# esp-sme.net
KiCad netlist of a schematic drawn in EAGLE
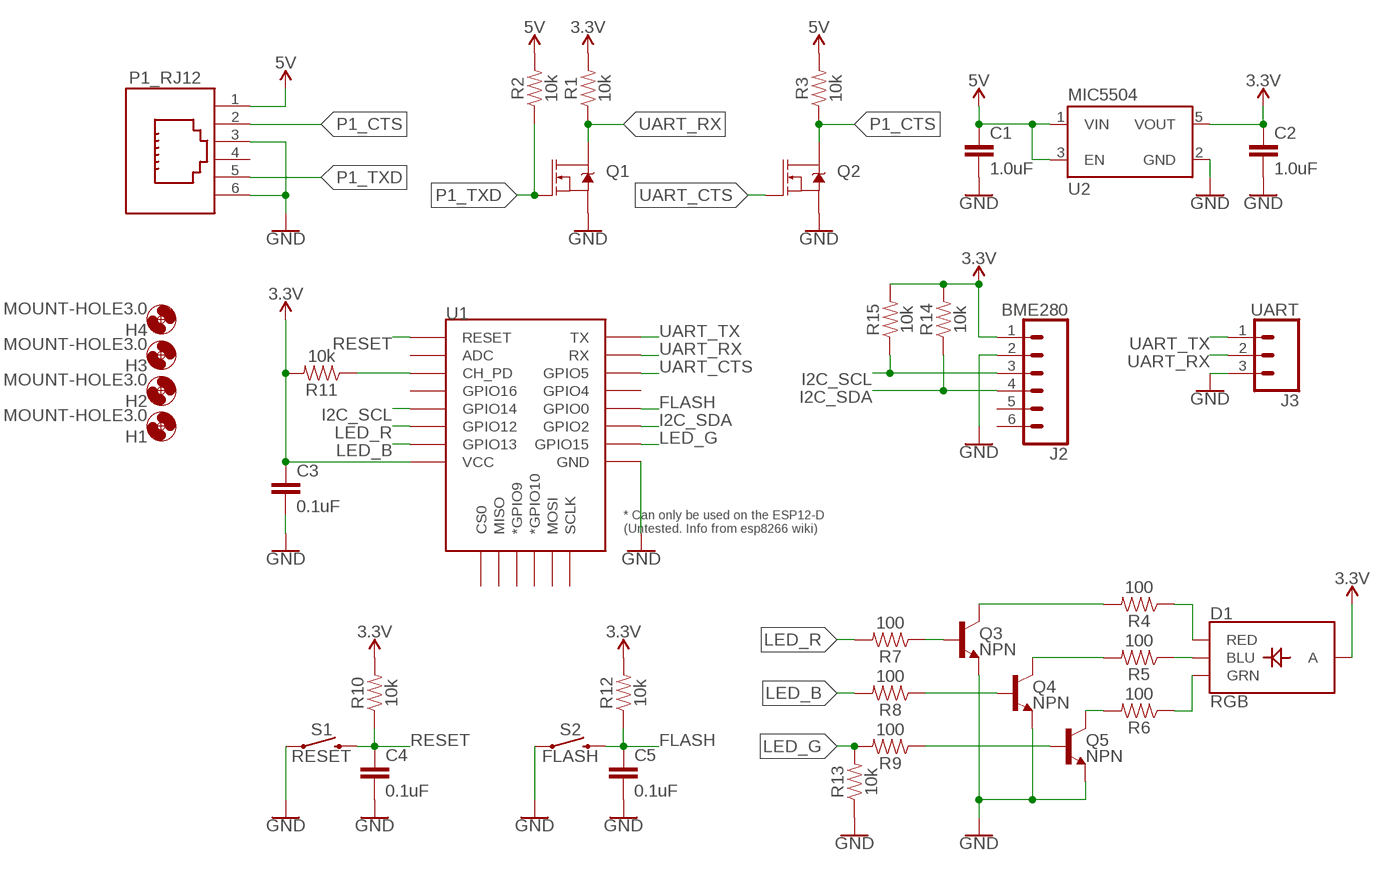
[diagram p0: schematic, sheet 1]

(export (version "E")
  (design (tool "Eeschema 10.0.6"))
  (components
    (comp (ref "C1")
      (value "1.0uF")
      (footprint "eagle-import:0603")
      (libsource (lib "eagle-import") (part "1.0UF-0603-16V-10%"))
    )
    (comp (ref "C2")
      (value "1.0uF")
      (footprint "eagle-import:0603")
      (libsource (lib "eagle-import") (part "1.0UF-0603-16V-10%"))
    )
    (comp (ref "C3")
      (value "0.1uF")
      (footprint "eagle-import:0603")
      (libsource (lib "eagle-import") (part "0.1UF-0603-25V-5%"))
    )
    (comp (ref "C4")
      (value "0.1uF")
      (footprint "eagle-import:0603")
      (libsource (lib "eagle-import") (part "0.1UF-0603-25V-5%"))
    )
    (comp (ref "C5")
      (value "0.1uF")
      (footprint "eagle-import:0603")
      (libsource (lib "eagle-import") (part "0.1UF-0603-25V-5%"))
    )
    (comp (ref "D1")
      (value "RGB")
      (footprint "eagle-import:P-LCC-4-3")
      (libsource (lib "eagle-import") (part "LED-RGB-CAPLCC"))
    )
    (comp (ref "H1")
      (value "MOUNT-HOLE3.0")
      (footprint "eagle-import:3,0")
      (libsource (lib "eagle-import") (part "MOUNT-HOLE3.0"))
    )
    (comp (ref "H2")
      (value "MOUNT-HOLE3.0")
      (footprint "eagle-import:3,0")
      (libsource (lib "eagle-import") (part "MOUNT-HOLE3.0"))
    )
    (comp (ref "H3")
      (value "MOUNT-HOLE3.0")
      (footprint "eagle-import:3,0")
      (libsource (lib "eagle-import") (part "MOUNT-HOLE3.0"))
    )
    (comp (ref "H4")
      (value "MOUNT-HOLE3.0")
      (footprint "eagle-import:3,0")
      (libsource (lib "eagle-import") (part "MOUNT-HOLE3.0"))
    )
    (comp (ref "J2")
      (value "BME280")
      (footprint "eagle-import:1X06")
      (libsource (lib "eagle-import") (part "CONN_06SILK_FEMALE_PTH"))
    )
    (comp (ref "J3")
      (value "UART")
      (footprint "eagle-import:1X03")
      (libsource (lib "eagle-import") (part "CONN_03"))
    )
    (comp (ref "P1_RJ12")
      (value "615006143621")
      (footprint "eagle-import:615006143621")
      (libsource (lib "eagle-import") (part "615006143621"))
    )
    (comp (ref "Q1")
      (value "MOSFET-NCH-AO3404A")
      (footprint "eagle-import:SOT23-3")
      (libsource (lib "eagle-import") (part "MOSFET-NCH-AO3404A"))
    )
    (comp (ref "Q2")
      (value "MOSFET-NCH-AO3404A")
      (footprint "eagle-import:SOT23-3")
      (libsource (lib "eagle-import") (part "MOSFET-NCH-AO3404A"))
    )
    (comp (ref "Q3")
      (value "NPN")
      (footprint "eagle-import:SOT23-3")
      (libsource (lib "eagle-import") (part "TRANS_NPN-MMBT2222AL"))
    )
    (comp (ref "Q4")
      (value "NPN")
      (footprint "eagle-import:SOT23-3")
      (libsource (lib "eagle-import") (part "TRANS_NPN-MMBT2222AL"))
    )
    (comp (ref "Q5")
      (value "NPN")
      (footprint "eagle-import:SOT23-3")
      (libsource (lib "eagle-import") (part "TRANS_NPN-MMBT2222AL"))
    )
    (comp (ref "R1")
      (value "10k")
      (footprint "eagle-import:0603")
      (libsource (lib "eagle-import") (part "10KOHM-0603-1/10W-1%"))
    )
    (comp (ref "R2")
      (value "10k")
      (footprint "eagle-import:0603")
      (libsource (lib "eagle-import") (part "10KOHM-0603-1/10W-1%"))
    )
    (comp (ref "R3")
      (value "10k")
      (footprint "eagle-import:0603")
      (libsource (lib "eagle-import") (part "10KOHM-0603-1/10W-1%"))
    )
    (comp (ref "R4")
      (value "100")
      (footprint "eagle-import:0603")
      (libsource (lib "eagle-import") (part "100OHM-0603-1/10W-1%"))
    )
    (comp (ref "R5")
      (value "100")
      (footprint "eagle-import:0603")
      (libsource (lib "eagle-import") (part "100OHM-0603-1/10W-1%"))
    )
    (comp (ref "R6")
      (value "100")
      (footprint "eagle-import:0603")
      (libsource (lib "eagle-import") (part "100OHM-0603-1/10W-1%"))
    )
    (comp (ref "R7")
      (value "100")
      (footprint "eagle-import:0603")
      (libsource (lib "eagle-import") (part "100OHM-0603-1/10W-1%"))
    )
    (comp (ref "R8")
      (value "100")
      (footprint "eagle-import:0603")
      (libsource (lib "eagle-import") (part "100OHM-0603-1/10W-1%"))
    )
    (comp (ref "R9")
      (value "100")
      (footprint "eagle-import:0603")
      (libsource (lib "eagle-import") (part "100OHM-0603-1/10W-1%"))
    )
    (comp (ref "R10")
      (value "10k")
      (footprint "eagle-import:0603")
      (libsource (lib "eagle-import") (part "10KOHM-0603-1/10W-1%"))
    )
    (comp (ref "R11")
      (value "10k")
      (footprint "eagle-import:0603")
      (libsource (lib "eagle-import") (part "10KOHM-0603-1/10W-1%"))
    )
    (comp (ref "R12")
      (value "10k")
      (footprint "eagle-import:0603")
      (libsource (lib "eagle-import") (part "10KOHM-0603-1/10W-1%"))
    )
    (comp (ref "R13")
      (value "10k")
      (footprint "eagle-import:0603")
      (libsource (lib "eagle-import") (part "10KOHM-0603-1/10W-1%"))
    )
    (comp (ref "R14")
      (value "10k")
      (footprint "eagle-import:0603")
      (libsource (lib "eagle-import") (part "10KOHM-0603-1/10W-1%"))
    )
    (comp (ref "R15")
      (value "10k")
      (footprint "eagle-import:0603")
      (libsource (lib "eagle-import") (part "10KOHM-0603-1/10W-1%"))
    )
    (comp (ref "S1")
      (value "RESET")
      (footprint "eagle-import:TACTILE_SWITCH_SMD_4.6X2.8MM")
      (libsource (lib "eagle-import") (part "MOMENTARY-SWITCH-SPST-SMD-4.6X2.8MM"))
    )
    (comp (ref "S2")
      (value "FLASH")
      (footprint "eagle-import:TACTILE_SWITCH_SMD_4.6X2.8MM")
      (libsource (lib "eagle-import") (part "MOMENTARY-SWITCH-SPST-SMD-4.6X2.8MM"))
    )
    (comp (ref "U1")
      (value "ESP12ESMD")
      (footprint "eagle-import:ESP12E-SMD")
      (libsource (lib "eagle-import") (part "ESP12ESMD"))
    )
    (comp (ref "U2")
      (value "MIC5504")
      (footprint "eagle-import:SOT23-5")
      (libsource (lib "eagle-import") (part "MIC5504"))
    )
  )
  (nets
    (net (code "1") (name "/FLASH") (class "Default")
      (node (ref "C5") (pin "1") (pinfunction "1_1") (pintype "passive"))
      (node (ref "R12") (pin "1") (pinfunction "1_1") (pintype "passive"))
      (node (ref "S2") (pin "3") (pinfunction "2_3") (pintype "passive"))
      (node (ref "S2") (pin "4") (pinfunction "2_4") (pintype "passive"))
      (node (ref "U1") (pin "GPIO0") (pinfunction "GPIO0_GPIO0") (pintype "bidirectional"))
    )
    (net (code "2") (name "/I2C_SCL") (class "Default")
      (node (ref "J2") (pin "3") (pinfunction "3_3") (pintype "passive"))
      (node (ref "R15") (pin "1") (pinfunction "1_1") (pintype "passive"))
      (node (ref "U1") (pin "GPIO14") (pinfunction "GPIO14_GPIO14") (pintype "bidirectional"))
    )
    (net (code "3") (name "/I2C_SDA") (class "Default")
      (node (ref "J2") (pin "4") (pinfunction "4_4") (pintype "passive"))
      (node (ref "R14") (pin "1") (pinfunction "1_1") (pintype "passive"))
      (node (ref "U1") (pin "GPIO2") (pinfunction "GPIO2_GPIO2") (pintype "bidirectional"))
    )
    (net (code "4") (name "/RESET") (class "Default")
      (node (ref "C4") (pin "1") (pinfunction "1_1") (pintype "passive"))
      (node (ref "R10") (pin "1") (pinfunction "1_1") (pintype "passive"))
      (node (ref "S1") (pin "3") (pinfunction "2_3") (pintype "passive"))
      (node (ref "S1") (pin "4") (pinfunction "2_4") (pintype "passive"))
      (node (ref "U1") (pin "RESET") (pinfunction "RESET_RESET") (pintype "bidirectional"))
    )
    (net (code "5") (name "/UART_TX") (class "Default")
      (node (ref "J3") (pin "1") (pinfunction "1_1") (pintype "passive"))
      (node (ref "U1") (pin "TXD0") (pinfunction "TX_TXD0") (pintype "bidirectional"))
    )
    (net (code "6") (name "3.3V") (class "Default")
      (node (ref "C2") (pin "1") (pinfunction "1_1") (pintype "passive"))
      (node (ref "C3") (pin "1") (pinfunction "1_1") (pintype "passive"))
      (node (ref "D1") (pin "4") (pinfunction "A_4") (pintype "bidirectional"))
      (node (ref "J2") (pin "1") (pinfunction "1_1") (pintype "passive"))
      (node (ref "R1") (pin "2") (pinfunction "2_2") (pintype "passive"))
      (node (ref "R10") (pin "2") (pinfunction "2_2") (pintype "passive"))
      (node (ref "R11") (pin "2") (pinfunction "2_2") (pintype "passive"))
      (node (ref "R12") (pin "2") (pinfunction "2_2") (pintype "passive"))
      (node (ref "R14") (pin "2") (pinfunction "2_2") (pintype "passive"))
      (node (ref "R15") (pin "2") (pinfunction "2_2") (pintype "passive"))
      (node (ref "U1") (pin "VCC") (pinfunction "VCC_VCC") (pintype "bidirectional"))
      (node (ref "U2") (pin "5") (pinfunction "VOUT_5") (pintype "bidirectional"))
    )
    (net (code "7") (name "5V") (class "Default")
      (node (ref "C1") (pin "1") (pinfunction "1_1") (pintype "passive"))
      (node (ref "P1_RJ12") (pin "1") (pinfunction "6_1") (pintype "passive"))
      (node (ref "R2") (pin "2") (pinfunction "2_2") (pintype "passive"))
      (node (ref "R3") (pin "2") (pinfunction "2_2") (pintype "passive"))
      (node (ref "U2") (pin "1") (pinfunction "VIN_1") (pintype "bidirectional"))
      (node (ref "U2") (pin "3") (pinfunction "EN_3") (pintype "bidirectional"))
    )
    (net (code "8") (name "GND") (class "Default")
      (node (ref "C1") (pin "2") (pinfunction "2_2") (pintype "passive"))
      (node (ref "C2") (pin "2") (pinfunction "2_2") (pintype "passive"))
      (node (ref "C3") (pin "2") (pinfunction "2_2") (pintype "passive"))
      (node (ref "C4") (pin "2") (pinfunction "2_2") (pintype "passive"))
      (node (ref "C5") (pin "2") (pinfunction "2_2") (pintype "passive"))
      (node (ref "J2") (pin "2") (pinfunction "2_2") (pintype "passive"))
      (node (ref "J3") (pin "3") (pinfunction "3_3") (pintype "passive"))
      (node (ref "P1_RJ12") (pin "3") (pinfunction "4_3") (pintype "passive"))
      (node (ref "P1_RJ12") (pin "6") (pinfunction "1_6") (pintype "passive"))
      (node (ref "Q1") (pin "2") (pinfunction "S_2") (pintype "bidirectional"))
      (node (ref "Q2") (pin "2") (pinfunction "S_2") (pintype "bidirectional"))
      (node (ref "Q3") (pin "2") (pinfunction "E_2") (pintype "passive"))
      (node (ref "Q4") (pin "2") (pinfunction "E_2") (pintype "passive"))
      (node (ref "Q5") (pin "2") (pinfunction "E_2") (pintype "passive"))
      (node (ref "R13") (pin "1") (pinfunction "1_1") (pintype "passive"))
      (node (ref "S1") (pin "1") (pinfunction "1_1") (pintype "passive"))
      (node (ref "S1") (pin "2") (pinfunction "1_2") (pintype "passive"))
      (node (ref "S2") (pin "1") (pinfunction "1_1") (pintype "passive"))
      (node (ref "S2") (pin "2") (pinfunction "1_2") (pintype "passive"))
      (node (ref "U1") (pin "GND") (pinfunction "GND_GND") (pintype "bidirectional"))
      (node (ref "U2") (pin "2") (pinfunction "GND_2") (pintype "bidirectional"))
    )
    (net (code "9") (name "LED_B") (class "Default")
      (node (ref "R8") (pin "2") (pinfunction "2_2") (pintype "passive"))
      (node (ref "U1") (pin "GPIO13") (pinfunction "GPIO13_GPIO13") (pintype "bidirectional"))
    )
    (net (code "10") (name "LED_G") (class "Default")
      (node (ref "R13") (pin "2") (pinfunction "2_2") (pintype "passive"))
      (node (ref "R9") (pin "2") (pinfunction "2_2") (pintype "passive"))
      (node (ref "U1") (pin "GPIO15") (pinfunction "GPIO15_GPIO15") (pintype "bidirectional"))
    )
    (net (code "11") (name "LED_R") (class "Default")
      (node (ref "R7") (pin "2") (pinfunction "2_2") (pintype "passive"))
      (node (ref "U1") (pin "GPIO12") (pinfunction "GPIO12_GPIO12") (pintype "bidirectional"))
    )
    (net (code "12") (name "Net-(D1-BLU)") (class "Default")
      (node (ref "D1") (pin "3") (pinfunction "BLU_3") (pintype "bidirectional"))
      (node (ref "R5") (pin "1") (pinfunction "1_1") (pintype "passive"))
    )
    (net (code "13") (name "Net-(D1-GRN)") (class "Default")
      (node (ref "D1") (pin "2") (pinfunction "GRN_2") (pintype "bidirectional"))
      (node (ref "R6") (pin "1") (pinfunction "1_1") (pintype "passive"))
    )
    (net (code "14") (name "Net-(D1-RED)") (class "Default")
      (node (ref "D1") (pin "1") (pinfunction "RED_1") (pintype "bidirectional"))
      (node (ref "R4") (pin "1") (pinfunction "1_1") (pintype "passive"))
    )
    (net (code "15") (name "Net-(Q3-B)") (class "Default")
      (node (ref "Q3") (pin "1") (pinfunction "B_1") (pintype "passive"))
      (node (ref "R7") (pin "1") (pinfunction "1_1") (pintype "passive"))
    )
    (net (code "16") (name "Net-(Q3-C)") (class "Default")
      (node (ref "Q3") (pin "3") (pinfunction "C_3") (pintype "passive"))
      (node (ref "R4") (pin "2") (pinfunction "2_2") (pintype "passive"))
    )
    (net (code "17") (name "Net-(Q4-B)") (class "Default")
      (node (ref "Q4") (pin "1") (pinfunction "B_1") (pintype "passive"))
      (node (ref "R8") (pin "1") (pinfunction "1_1") (pintype "passive"))
    )
    (net (code "18") (name "Net-(Q4-C)") (class "Default")
      (node (ref "Q4") (pin "3") (pinfunction "C_3") (pintype "passive"))
      (node (ref "R5") (pin "2") (pinfunction "2_2") (pintype "passive"))
    )
    (net (code "19") (name "Net-(Q5-B)") (class "Default")
      (node (ref "Q5") (pin "1") (pinfunction "B_1") (pintype "passive"))
      (node (ref "R9") (pin "1") (pinfunction "1_1") (pintype "passive"))
    )
    (net (code "20") (name "Net-(Q5-C)") (class "Default")
      (node (ref "Q5") (pin "3") (pinfunction "C_3") (pintype "passive"))
      (node (ref "R6") (pin "2") (pinfunction "2_2") (pintype "passive"))
    )
    (net (code "21") (name "Net-(R11-Pad1)") (class "Default")
      (node (ref "R11") (pin "1") (pinfunction "1_1") (pintype "passive"))
      (node (ref "U1") (pin "CH_PD") (pinfunction "CH_PD_CH_PD") (pintype "bidirectional"))
    )
    (net (code "22") (name "P1_CTS") (class "Default")
      (node (ref "P1_RJ12") (pin "2") (pinfunction "5_2") (pintype "passive"))
      (node (ref "Q2") (pin "3") (pinfunction "D_3") (pintype "bidirectional"))
      (node (ref "R3") (pin "1") (pinfunction "1_1") (pintype "passive"))
    )
    (net (code "23") (name "P1_TXD") (class "Default")
      (node (ref "P1_RJ12") (pin "5") (pinfunction "2_5") (pintype "passive"))
      (node (ref "Q1") (pin "1") (pinfunction "G_1") (pintype "bidirectional"))
      (node (ref "R2") (pin "1") (pinfunction "1_1") (pintype "passive"))
    )
    (net (code "24") (name "UART_CTS") (class "Default")
      (node (ref "Q2") (pin "1") (pinfunction "G_1") (pintype "bidirectional"))
      (node (ref "U1") (pin "GPIO5") (pinfunction "GPIO5_GPIO5") (pintype "bidirectional"))
    )
    (net (code "25") (name "UART_RX") (class "Default")
      (node (ref "J3") (pin "2") (pinfunction "2_2") (pintype "passive"))
      (node (ref "Q1") (pin "3") (pinfunction "D_3") (pintype "bidirectional"))
      (node (ref "R1") (pin "1") (pinfunction "1_1") (pintype "passive"))
      (node (ref "U1") (pin "RXD0") (pinfunction "RX_RXD0") (pintype "bidirectional"))
    )
    (net (code "26") (name "unconnected-(J2-Pad5)") (class "Default")
      (node (ref "J2") (pin "5") (pinfunction "5_5") (pintype "passive"))
    )
    (net (code "27") (name "unconnected-(J2-Pad6)") (class "Default")
      (node (ref "J2") (pin "6") (pinfunction "6_6") (pintype "passive"))
    )
    (net (code "28") (name "unconnected-(P1_RJ12-3-Pad4)") (class "Default")
      (node (ref "P1_RJ12") (pin "4") (pinfunction "3_4") (pintype "passive"))
    )
    (net (code "29") (name "unconnected-(U1-*GPIO9-PadGPIO9)") (class "Default")
      (node (ref "U1") (pin "GPIO9") (pinfunction "*GPIO9_GPIO9") (pintype "bidirectional"))
    )
    (net (code "30") (name "unconnected-(U1-*GPIO10-PadGPIO10)") (class "Default")
      (node (ref "U1") (pin "GPIO10") (pinfunction "*GPIO10_GPIO10") (pintype "bidirectional"))
    )
    (net (code "31") (name "unconnected-(U1-PadADC)") (class "Default")
      (node (ref "U1") (pin "ADC") (pinfunction "ADC_ADC") (pintype "bidirectional"))
    )
    (net (code "32") (name "unconnected-(U1-PadCS0)") (class "Default")
      (node (ref "U1") (pin "CS0") (pinfunction "CS0_CS0") (pintype "bidirectional"))
    )
    (net (code "33") (name "unconnected-(U1-PadGPIO4)") (class "Default")
      (node (ref "U1") (pin "GPIO4") (pinfunction "GPIO4_GPIO4") (pintype "bidirectional"))
    )
    (net (code "34") (name "unconnected-(U1-PadGPIO16)") (class "Default")
      (node (ref "U1") (pin "GPIO16") (pinfunction "GPIO16_GPIO16") (pintype "bidirectional"))
    )
    (net (code "35") (name "unconnected-(U1-PadMISO)") (class "Default")
      (node (ref "U1") (pin "MISO") (pinfunction "MISO_MISO") (pintype "bidirectional"))
    )
    (net (code "36") (name "unconnected-(U1-PadMOSI)") (class "Default")
      (node (ref "U1") (pin "MOSI") (pinfunction "MOSI_MOSI") (pintype "bidirectional"))
    )
    (net (code "37") (name "unconnected-(U1-PadSCLK)") (class "Default")
      (node (ref "U1") (pin "SCLK") (pinfunction "SCLK_SCLK") (pintype "bidirectional"))
    )
  )
)
